# eye_of_horus_v1.net
KiCad netlist of a schematic drawn in EAGLE
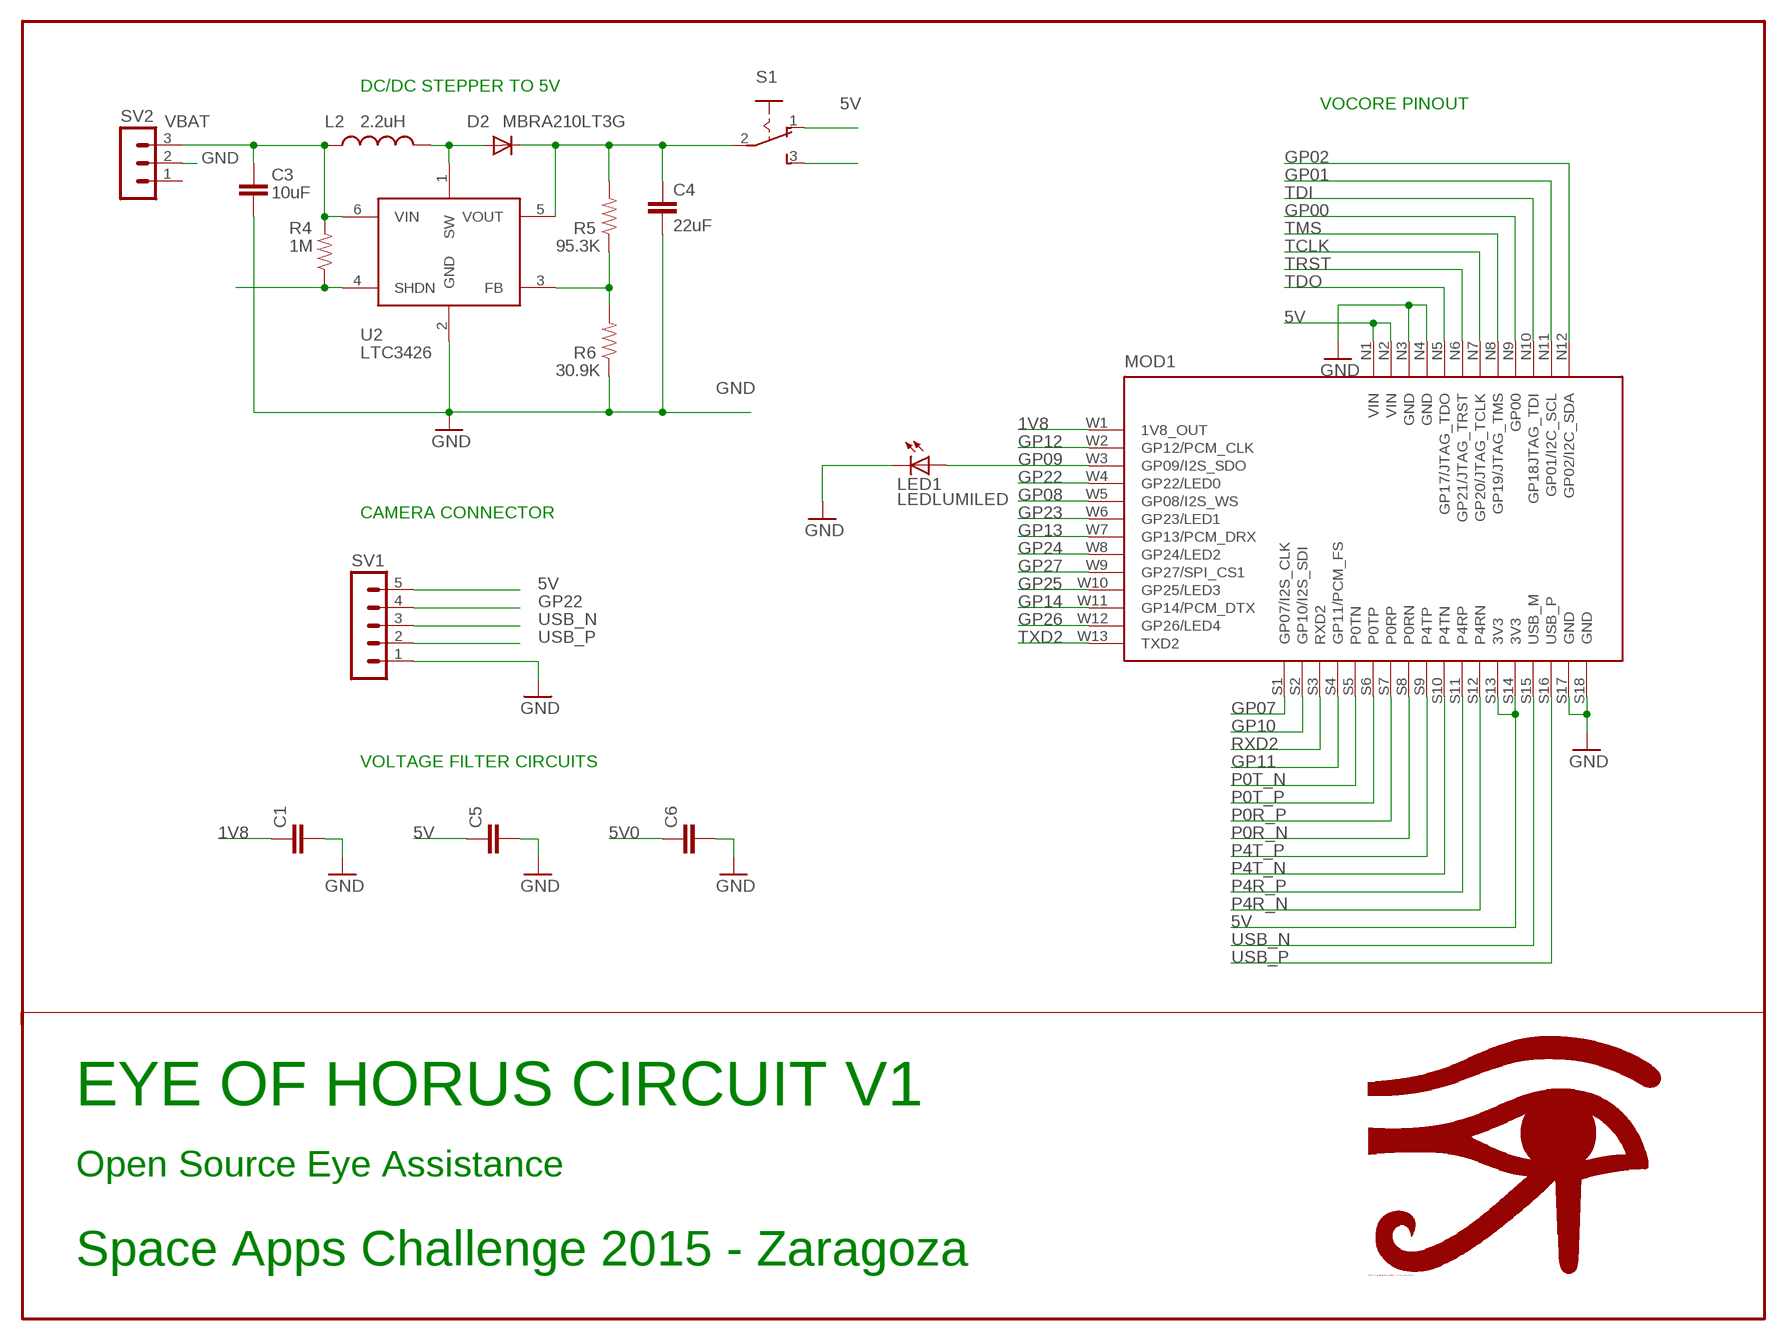
[diagram p0: schematic, sheet 1]

(export (version "E")
  (design (tool "Eeschema 10.0.6"))
  (components
    (comp (ref "C1")
      (value "C-EUC0805")
      (footprint "eagle-import:C0805")
      (libsource (lib "eagle-import") (part "C-EUC0805"))
    )
    (comp (ref "C3")
      (value "10uF")
      (footprint "eagle-import:0603")
      (libsource (lib "eagle-import") (part "CAP0603"))
    )
    (comp (ref "C4")
      (value "22uF")
      (footprint "eagle-import:1206")
      (libsource (lib "eagle-import") (part "CAP1206"))
    )
    (comp (ref "C5")
      (value "C-EUC0805")
      (footprint "eagle-import:C0805")
      (libsource (lib "eagle-import") (part "C-EUC0805"))
    )
    (comp (ref "C6")
      (value "C-EUC0805")
      (footprint "eagle-import:C0805")
      (libsource (lib "eagle-import") (part "C-EUC0805"))
    )
    (comp (ref "D2")
      (value "MBRA210LT3G")
      (footprint "eagle-import:SMA-DIODE")
      (libsource (lib "eagle-import") (part "DIODESMA"))
    )
    (comp (ref "L2")
      (value "2.2uH")
      (footprint "eagle-import:1_3X1_3")
      (libsource (lib "eagle-import") (part "INDUCTOR1313"))
    )
    (comp (ref "LED1")
      (value "LEDLUMILED")
      (footprint "eagle-import:LUMILED")
      (libsource (lib "eagle-import") (part "LEDLUMILED"))
    )
    (comp (ref "MOD1")
      (value "VOCORE_V10A")
      (footprint "eagle-import:VOCORE_V10A")
      (libsource (lib "eagle-import") (part "VOCORE_V10A"))
    )
    (comp (ref "R4")
      (value "1M")
      (footprint "eagle-import:0603")
      (libsource (lib "eagle-import") (part "RESISTOR0603"))
    )
    (comp (ref "R5")
      (value "95.3K")
      (footprint "eagle-import:0603")
      (libsource (lib "eagle-import") (part "RESISTOR0603"))
    )
    (comp (ref "R6")
      (value "30.9K")
      (footprint "eagle-import:0603")
      (libsource (lib "eagle-import") (part "RESISTOR0603"))
    )
    (comp (ref "S1")
      (value "255SB")
      (footprint "eagle-import:255SB")
      (libsource (lib "eagle-import") (part "255SB"))
    )
    (comp (ref "SV1")
      (value "MA05-1")
      (footprint "eagle-import:MA05-1")
      (libsource (lib "eagle-import") (part "MA05-1"))
    )
    (comp (ref "SV2")
      (value "MA03-1")
      (footprint "eagle-import:MA03-1")
      (libsource (lib "eagle-import") (part "MA03-1"))
    )
    (comp (ref "U2")
      (value "LTC3426")
      (footprint "eagle-import:SOT23-6")
      (libsource (lib "eagle-import") (part "LTC3426"))
    )
  )
  (nets
    (net (code "1") (name "/1V8") (class "Default")
      (node (ref "C1") (pin "1") (pinfunction "1_1") (pintype "passive"))
      (node (ref "MOD1") (pin "W1") (pinfunction "1V8_OUT_W1") (pintype "power_in"))
    )
    (net (code "2") (name "/5V") (class "Default")
      (node (ref "C5") (pin "1") (pinfunction "1_1") (pintype "passive"))
      (node (ref "MOD1") (pin "N1") (pinfunction "VIN_N1") (pintype "power_in"))
      (node (ref "MOD1") (pin "N2") (pinfunction "VIN_N2") (pintype "power_in"))
      (node (ref "MOD1") (pin "S13") (pinfunction "3V3_S13") (pintype "bidirectional"))
      (node (ref "MOD1") (pin "S14") (pinfunction "3V3_S14") (pintype "bidirectional"))
      (node (ref "S1") (pin "1") (pinfunction "O_1") (pintype "passive"))
      (node (ref "SV1") (pin "5") (pinfunction "5_5") (pintype "passive"))
    )
    (net (code "3") (name "/5V0") (class "Default")
      (node (ref "C6") (pin "1") (pinfunction "1_1") (pintype "passive"))
    )
    (net (code "4") (name "/GP00") (class "Default")
      (node (ref "MOD1") (pin "N9") (pinfunction "GP00_N9") (pintype "bidirectional"))
    )
    (net (code "5") (name "/GP01") (class "Default")
      (node (ref "MOD1") (pin "N11") (pinfunction "GP01/I2C_SCL_N11") (pintype "bidirectional"))
    )
    (net (code "6") (name "/GP02") (class "Default")
      (node (ref "MOD1") (pin "N12") (pinfunction "GP02/I2C_SDA_N12") (pintype "bidirectional"))
    )
    (net (code "7") (name "/GP07") (class "Default")
      (node (ref "MOD1") (pin "S1") (pinfunction "GP07/I2S_CLK_S1") (pintype "bidirectional"))
    )
    (net (code "8") (name "/GP08") (class "Default")
      (node (ref "MOD1") (pin "W5") (pinfunction "GP08/I2S_WS_W5") (pintype "bidirectional"))
    )
    (net (code "9") (name "/GP09") (class "Default")
      (node (ref "LED1") (pin "2+") (pinfunction "A_2+") (pintype "passive"))
      (node (ref "MOD1") (pin "W3") (pinfunction "GP09/I2S_SDO_W3") (pintype "bidirectional"))
    )
    (net (code "10") (name "/GP10") (class "Default")
      (node (ref "MOD1") (pin "S2") (pinfunction "GP10/I2S_SDI_S2") (pintype "bidirectional"))
    )
    (net (code "11") (name "/GP11") (class "Default")
      (node (ref "MOD1") (pin "S4") (pinfunction "GP11/PCM_FS_S4") (pintype "bidirectional"))
    )
    (net (code "12") (name "/GP12") (class "Default")
      (node (ref "MOD1") (pin "W2") (pinfunction "GP12/PCM_CLK_W2") (pintype "bidirectional"))
    )
    (net (code "13") (name "/GP13") (class "Default")
      (node (ref "MOD1") (pin "W7") (pinfunction "GP13/PCM_DRX_W7") (pintype "bidirectional"))
    )
    (net (code "14") (name "/GP14") (class "Default")
      (node (ref "MOD1") (pin "W11") (pinfunction "GP14/PCM_DTX_W11") (pintype "bidirectional"))
    )
    (net (code "15") (name "/GP22") (class "Default")
      (node (ref "MOD1") (pin "W4") (pinfunction "GP22/LED0_W4") (pintype "bidirectional"))
      (node (ref "SV1") (pin "4") (pinfunction "4_4") (pintype "passive"))
    )
    (net (code "16") (name "/GP23") (class "Default")
      (node (ref "MOD1") (pin "W6") (pinfunction "GP23/LED1_W6") (pintype "bidirectional"))
    )
    (net (code "17") (name "/GP24") (class "Default")
      (node (ref "MOD1") (pin "W8") (pinfunction "GP24/LED2_W8") (pintype "bidirectional"))
    )
    (net (code "18") (name "/GP25") (class "Default")
      (node (ref "MOD1") (pin "W10") (pinfunction "GP25/LED3_W10") (pintype "bidirectional"))
    )
    (net (code "19") (name "/GP26") (class "Default")
      (node (ref "MOD1") (pin "W12") (pinfunction "GP26/LED4_W12") (pintype "bidirectional"))
    )
    (net (code "20") (name "/GP27") (class "Default")
      (node (ref "MOD1") (pin "W9") (pinfunction "GP27/SPI_CS1_W9") (pintype "bidirectional"))
    )
    (net (code "21") (name "/P0R_N") (class "Default")
      (node (ref "MOD1") (pin "S8") (pinfunction "P0RN_S8") (pintype "bidirectional"))
    )
    (net (code "22") (name "/P0R_P") (class "Default")
      (node (ref "MOD1") (pin "S7") (pinfunction "P0RP_S7") (pintype "bidirectional"))
    )
    (net (code "23") (name "/P0T_N") (class "Default")
      (node (ref "MOD1") (pin "S5") (pinfunction "P0TN_S5") (pintype "bidirectional"))
    )
    (net (code "24") (name "/P0T_P") (class "Default")
      (node (ref "MOD1") (pin "S6") (pinfunction "P0TP_S6") (pintype "bidirectional"))
    )
    (net (code "25") (name "/P4R_N") (class "Default")
      (node (ref "MOD1") (pin "S12") (pinfunction "P4RN_S12") (pintype "bidirectional"))
    )
    (net (code "26") (name "/P4R_P") (class "Default")
      (node (ref "MOD1") (pin "S11") (pinfunction "P4RP_S11") (pintype "bidirectional"))
    )
    (net (code "27") (name "/P4T_N") (class "Default")
      (node (ref "MOD1") (pin "S10") (pinfunction "P4TN_S10") (pintype "bidirectional"))
    )
    (net (code "28") (name "/P4T_P") (class "Default")
      (node (ref "MOD1") (pin "S9") (pinfunction "P4TP_S9") (pintype "bidirectional"))
    )
    (net (code "29") (name "/RXD2") (class "Default")
      (node (ref "MOD1") (pin "S3") (pinfunction "RXD2_S3") (pintype "bidirectional"))
    )
    (net (code "30") (name "/TCLK") (class "Default")
      (node (ref "MOD1") (pin "N7") (pinfunction "GP20/JTAG_TCLK_N7") (pintype "bidirectional"))
    )
    (net (code "31") (name "/TDI") (class "Default")
      (node (ref "MOD1") (pin "N10") (pinfunction "GP18JTAG_TDI_N10") (pintype "bidirectional"))
    )
    (net (code "32") (name "/TDO") (class "Default")
      (node (ref "MOD1") (pin "N5") (pinfunction "GP17/JTAG_TDO_N5") (pintype "bidirectional"))
    )
    (net (code "33") (name "/TMS") (class "Default")
      (node (ref "MOD1") (pin "N8") (pinfunction "GP19/JTAG_TMS_N8") (pintype "bidirectional"))
    )
    (net (code "34") (name "/TRST") (class "Default")
      (node (ref "MOD1") (pin "N6") (pinfunction "GP21/JTAG_TRST_N6") (pintype "bidirectional"))
    )
    (net (code "35") (name "/TXD2") (class "Default")
      (node (ref "MOD1") (pin "W13") (pinfunction "TXD2_W13") (pintype "bidirectional"))
    )
    (net (code "36") (name "/USB_N") (class "Default")
      (node (ref "MOD1") (pin "S15") (pinfunction "USB_M_S15") (pintype "bidirectional"))
      (node (ref "SV1") (pin "3") (pinfunction "3_3") (pintype "passive"))
    )
    (net (code "37") (name "/USB_P") (class "Default")
      (node (ref "MOD1") (pin "S16") (pinfunction "USB_P_S16") (pintype "bidirectional"))
      (node (ref "SV1") (pin "2") (pinfunction "2_2") (pintype "passive"))
    )
    (net (code "38") (name "/VBAT") (class "Default")
      (node (ref "C3") (pin "1") (pinfunction "1_1") (pintype "passive"))
      (node (ref "L2") (pin "P$1") (pinfunction "1_P$1") (pintype "passive"))
      (node (ref "R4") (pin "2") (pinfunction "2_2") (pintype "passive"))
      (node (ref "SV2") (pin "3") (pinfunction "3_3") (pintype "passive"))
      (node (ref "U2") (pin "6") (pinfunction "VIN_6") (pintype "power_in"))
    )
    (net (code "39") (name "GND") (class "Default")
      (node (ref "C1") (pin "2") (pinfunction "2_2") (pintype "passive"))
      (node (ref "C3") (pin "2") (pinfunction "2_2") (pintype "passive"))
      (node (ref "C4") (pin "2") (pinfunction "2_2") (pintype "passive"))
      (node (ref "C5") (pin "2") (pinfunction "2_2") (pintype "passive"))
      (node (ref "C6") (pin "2") (pinfunction "2_2") (pintype "passive"))
      (node (ref "LED1") (pin "4-") (pinfunction "C_4-") (pintype "passive"))
      (node (ref "MOD1") (pin "N3") (pinfunction "GND_N3") (pintype "power_in"))
      (node (ref "MOD1") (pin "N4") (pinfunction "GND_N4") (pintype "power_in"))
      (node (ref "MOD1") (pin "S17") (pinfunction "GND_S17") (pintype "power_in"))
      (node (ref "MOD1") (pin "S18") (pinfunction "GND_S18") (pintype "power_in"))
      (node (ref "R6") (pin "1") (pinfunction "1_1") (pintype "passive"))
      (node (ref "SV1") (pin "1") (pinfunction "1_1") (pintype "passive"))
      (node (ref "SV2") (pin "2") (pinfunction "2_2") (pintype "passive"))
      (node (ref "U2") (pin "2") (pinfunction "GND_2") (pintype "passive"))
    )
    (net (code "40") (name "Net-(L2-2)") (class "Default")
      (node (ref "D2") (pin "A") (pinfunction "A_A") (pintype "passive"))
      (node (ref "L2") (pin "P$2") (pinfunction "2_P$2") (pintype "passive"))
      (node (ref "U2") (pin "1") (pinfunction "SW_1") (pintype "passive"))
    )
    (net (code "41") (name "Net-(S1-P)") (class "Default")
      (node (ref "C4") (pin "1") (pinfunction "1_1") (pintype "passive"))
      (node (ref "D2") (pin "C") (pinfunction "C_C") (pintype "passive"))
      (node (ref "R5") (pin "2") (pinfunction "2_2") (pintype "passive"))
      (node (ref "S1") (pin "2") (pinfunction "P_2") (pintype "passive"))
      (node (ref "U2") (pin "5") (pinfunction "VOUT_5") (pintype "passive"))
    )
    (net (code "42") (name "Net-(U2-FB)") (class "Default")
      (node (ref "R5") (pin "1") (pinfunction "1_1") (pintype "passive"))
      (node (ref "R6") (pin "2") (pinfunction "2_2") (pintype "passive"))
      (node (ref "U2") (pin "3") (pinfunction "FB_3") (pintype "input"))
    )
    (net (code "43") (name "Net-(U2-SHDN)") (class "Default")
      (node (ref "R4") (pin "1") (pinfunction "1_1") (pintype "passive"))
      (node (ref "U2") (pin "4") (pinfunction "SHDN_4") (pintype "input"))
    )
    (net (code "44") (name "unconnected-(S1-S-Pad3)") (class "Default")
      (node (ref "S1") (pin "3") (pinfunction "S_3") (pintype "passive"))
    )
    (net (code "45") (name "unconnected-(SV2-Pad1)") (class "Default")
      (node (ref "SV2") (pin "1") (pinfunction "1_1") (pintype "passive"))
    )
  )
)
